# wdt.net
KiCad netlist of a schematic drawn in EAGLE
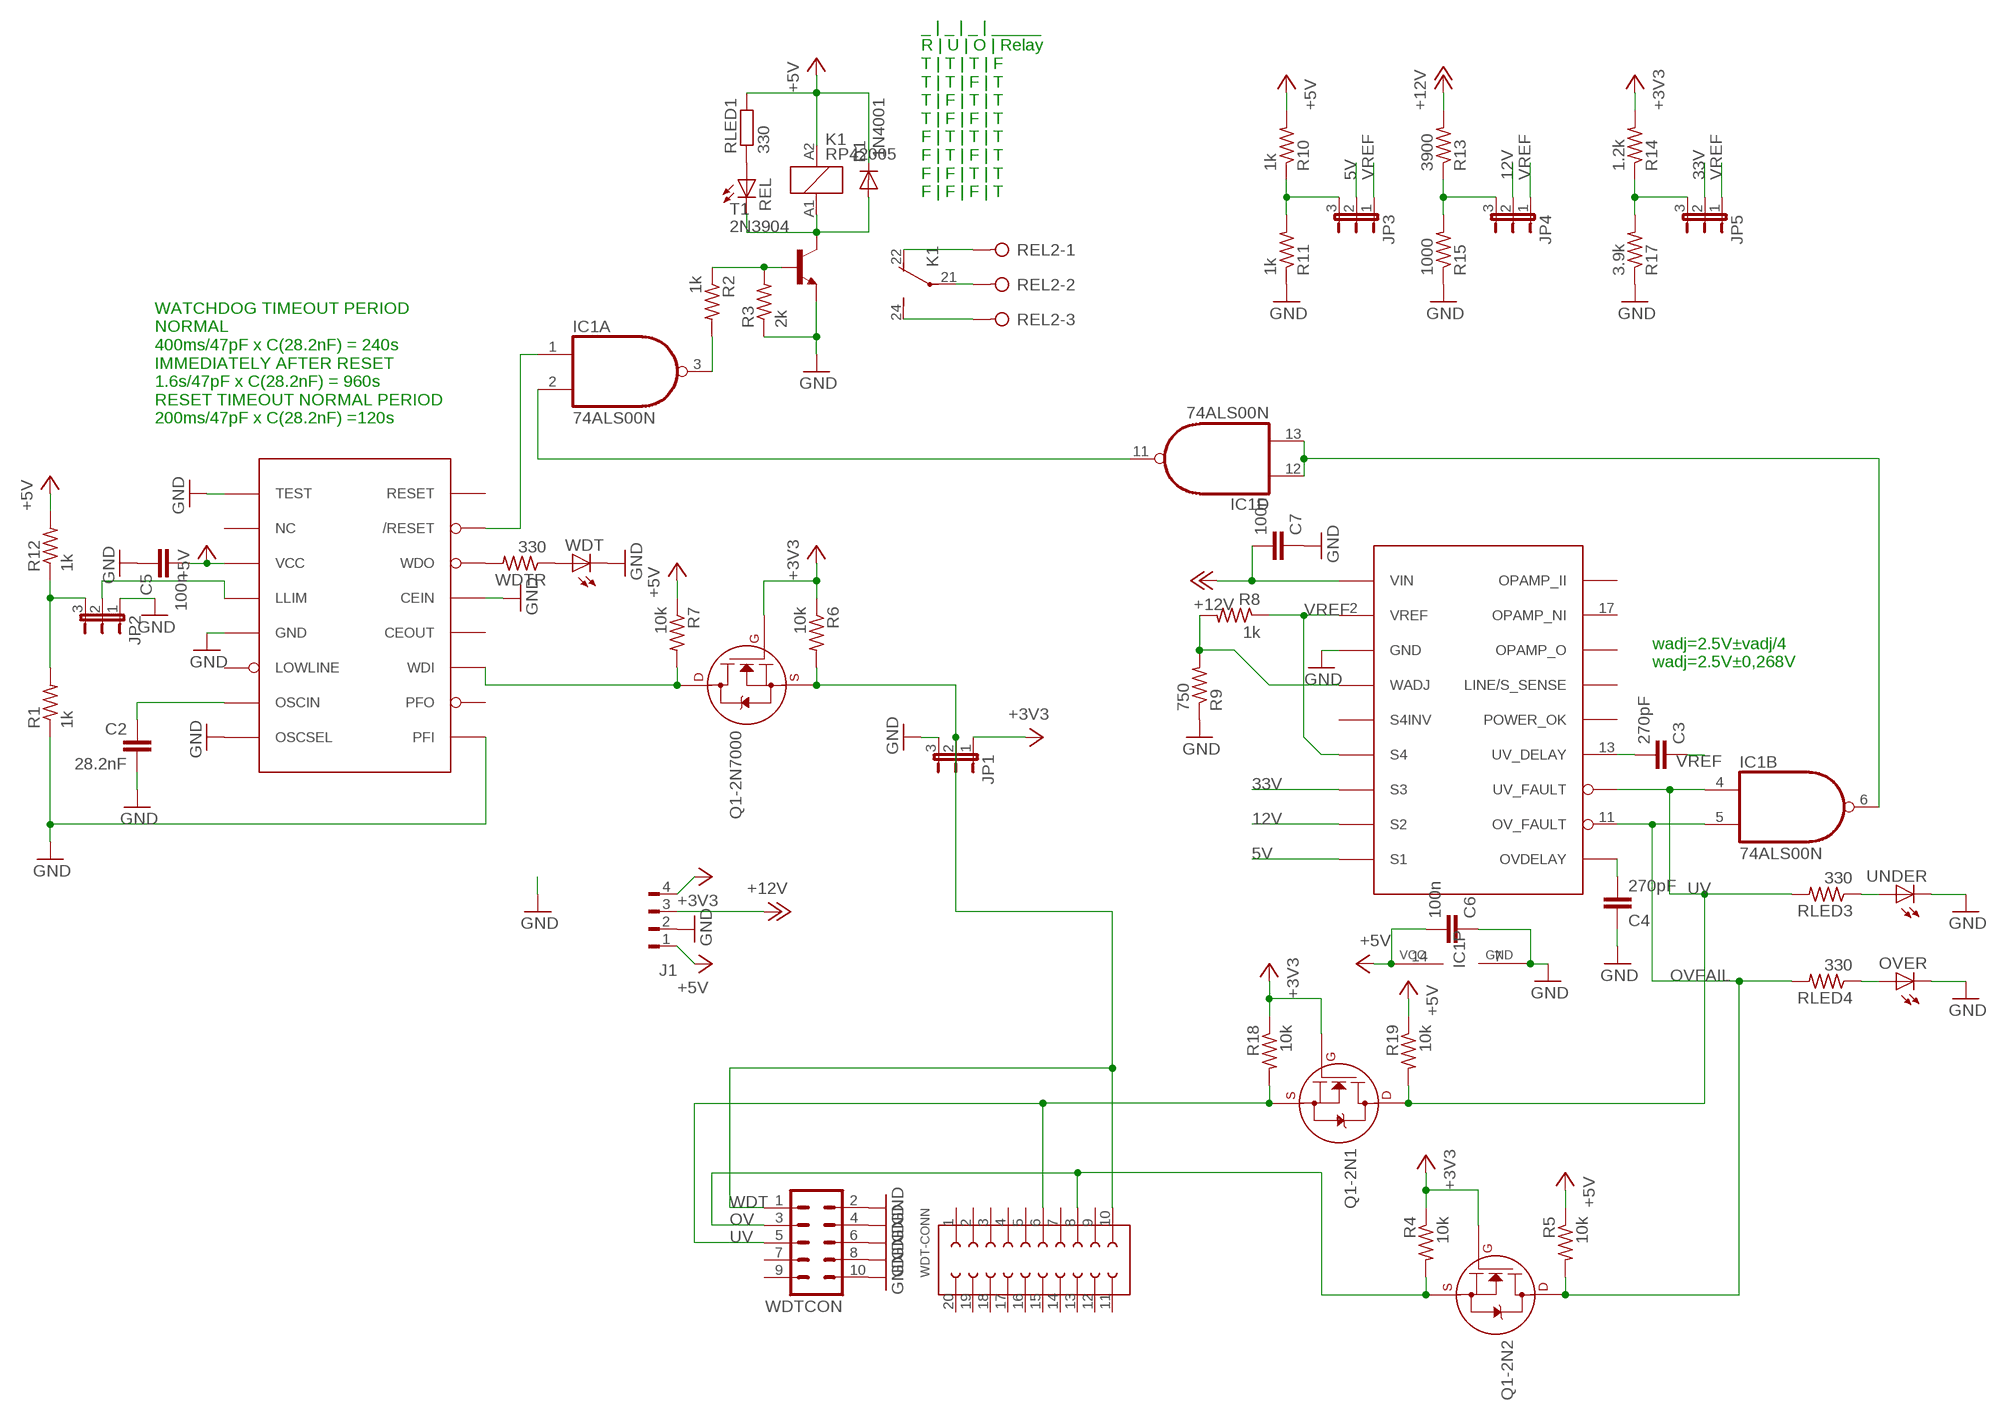
[diagram p0: schematic, sheet 1]

(export (version "E")
  (design (tool "Eeschema 10.0.6"))
  (components
    (comp (ref "C2")
      (value "28.2nF")
      (footprint "eagle-import:C050-025X075")
      (libsource (lib "eagle-import") (part "C-EU050-025X075"))
    )
    (comp (ref "C3")
      (value "270pF")
      (footprint "eagle-import:C050-025X075")
      (libsource (lib "eagle-import") (part "C-EU050-025X075"))
    )
    (comp (ref "C4")
      (value "270pF")
      (footprint "eagle-import:C050-025X075")
      (libsource (lib "eagle-import") (part "C-EU050-025X075"))
    )
    (comp (ref "C5")
      (value "100n")
      (footprint "eagle-import:C050-025X075")
      (libsource (lib "eagle-import") (part "C-EU050-025X075"))
    )
    (comp (ref "C6")
      (value "100n")
      (footprint "eagle-import:C050-025X075")
      (libsource (lib "eagle-import") (part "C-EU050-025X075"))
    )
    (comp (ref "C7")
      (value "100n")
      (footprint "eagle-import:C050-025X075")
      (libsource (lib "eagle-import") (part "C-EU050-025X075"))
    )
    (comp (ref "D1")
      (value "1N4001")
      (footprint "eagle-import:DO41-10")
      (libsource (lib "eagle-import") (part "1N4004"))
    )
    (comp (ref "IC1")
      (value "74ALS00N")
      (footprint "eagle-import:DIL14")
      (libsource (lib "eagle-import") (part "7400NALS"))
    )
    (comp (ref "J1")
      (value "FLOP-4W827001")
      (footprint "eagle-import:827001")
      (libsource (lib "eagle-import") (part "FLOP-4W827001"))
    )
    (comp (ref "JP1")
      (value "JP2E")
      (footprint "eagle-import:JP2")
      (libsource (lib "eagle-import") (part "JP2E"))
    )
    (comp (ref "JP2")
      (value "JP2E")
      (footprint "eagle-import:JP2")
      (libsource (lib "eagle-import") (part "JP2E"))
    )
    (comp (ref "JP3")
      (value "JP2E")
      (footprint "eagle-import:JP2")
      (libsource (lib "eagle-import") (part "JP2E"))
    )
    (comp (ref "JP4")
      (value "JP2E")
      (footprint "eagle-import:JP2")
      (libsource (lib "eagle-import") (part "JP2E"))
    )
    (comp (ref "JP5")
      (value "JP2E")
      (footprint "eagle-import:JP2")
      (libsource (lib "eagle-import") (part "JP2E"))
    )
    (comp (ref "K1")
      (value "RP42005")
      (footprint "eagle-import:RP420")
      (fields (field (name "MF") "TYCO ELECTRONICS") (field (name "MPN") "RP420024"))
      (libsource (lib "eagle-import") (part "RP42?0024"))
    )
    (comp (ref "OVER")
      (value "LED3MM")
      (footprint "eagle-import:LED3MM")
      (libsource (lib "eagle-import") (part "LED3MM"))
    )
    (comp (ref "Q1-2N1")
      (value "2N7000_TO92")
      (footprint "eagle-import:TO-92")
      (libsource (lib "eagle-import") (part "2N700_TO920"))
    )
    (comp (ref "Q1-2N2")
      (value "2N7000_TO92")
      (footprint "eagle-import:TO-92")
      (libsource (lib "eagle-import") (part "2N700_TO920"))
    )
    (comp (ref "Q1-2N7000")
      (value "2N7000_TO92")
      (footprint "eagle-import:TO-92")
      (libsource (lib "eagle-import") (part "2N700_TO920"))
    )
    (comp (ref "R1")
      (value "1k")
      (footprint "eagle-import:0207_10")
      (libsource (lib "eagle-import") (part "R-US_0207/10"))
    )
    (comp (ref "R2")
      (value "1k")
      (footprint "eagle-import:0207_10")
      (libsource (lib "eagle-import") (part "R-US_0207/10"))
    )
    (comp (ref "R3")
      (value "2k")
      (footprint "eagle-import:0207_10")
      (libsource (lib "eagle-import") (part "R-US_0207/10"))
    )
    (comp (ref "R4")
      (value "10k")
      (footprint "eagle-import:0207_10")
      (libsource (lib "eagle-import") (part "R-US_0207/10"))
    )
    (comp (ref "R5")
      (value "10k")
      (footprint "eagle-import:0207_10")
      (libsource (lib "eagle-import") (part "R-US_0207/10"))
    )
    (comp (ref "R6")
      (value "10k")
      (footprint "eagle-import:0207_10")
      (libsource (lib "eagle-import") (part "R-US_0207/10"))
    )
    (comp (ref "R7")
      (value "10k")
      (footprint "eagle-import:0207_10")
      (libsource (lib "eagle-import") (part "R-US_0207/10"))
    )
    (comp (ref "R8")
      (value "1k")
      (footprint "eagle-import:0207_10")
      (libsource (lib "eagle-import") (part "R-US_0207/10"))
    )
    (comp (ref "R9")
      (value "750")
      (footprint "eagle-import:0207_10")
      (libsource (lib "eagle-import") (part "R-US_0207/10"))
    )
    (comp (ref "R10")
      (value "1k")
      (footprint "eagle-import:0207_10")
      (libsource (lib "eagle-import") (part "R-US_0207/10"))
    )
    (comp (ref "R11")
      (value "1k")
      (footprint "eagle-import:0207_10")
      (libsource (lib "eagle-import") (part "R-US_0207/10"))
    )
    (comp (ref "R12")
      (value "1k")
      (footprint "eagle-import:0207_10")
      (libsource (lib "eagle-import") (part "R-US_0207/10"))
    )
    (comp (ref "R13")
      (value "3900")
      (footprint "eagle-import:0207_10")
      (libsource (lib "eagle-import") (part "R-US_0207/10"))
    )
    (comp (ref "R14")
      (value "1.2k")
      (footprint "eagle-import:0207_10")
      (libsource (lib "eagle-import") (part "R-US_0207/10"))
    )
    (comp (ref "R15")
      (value "1000")
      (footprint "eagle-import:0207_10")
      (libsource (lib "eagle-import") (part "R-US_0207/10"))
    )
    (comp (ref "R17")
      (value "3.9k")
      (footprint "eagle-import:0207_10")
      (libsource (lib "eagle-import") (part "R-US_0207/10"))
    )
    (comp (ref "R18")
      (value "10k")
      (footprint "eagle-import:0207_10")
      (libsource (lib "eagle-import") (part "R-US_0207/10"))
    )
    (comp (ref "R19")
      (value "10k")
      (footprint "eagle-import:0207_10")
      (libsource (lib "eagle-import") (part "R-US_0207/10"))
    )
    (comp (ref "REL")
      (value "LED3MM")
      (footprint "eagle-import:LED3MM")
      (libsource (lib "eagle-import") (part "LED3MM"))
    )
    (comp (ref "REL2")
      (value "W237-3E")
      (footprint "eagle-import:W237-3E")
      (fields (field (name "OC_FARNELL") "unknown") (field (name "OC_NEWARK") "unknown"))
      (libsource (lib "eagle-import") (part "W237-3E"))
    )
    (comp (ref "RLED1")
      (value "330")
      (footprint "eagle-import:0207_10")
      (libsource (lib "eagle-import") (part "R-EU_0207/10"))
    )
    (comp (ref "RLED3")
      (value "330")
      (footprint "eagle-import:0207_10")
      (libsource (lib "eagle-import") (part "R-US_0207/10"))
    )
    (comp (ref "RLED4")
      (value "330")
      (footprint "eagle-import:0207_10")
      (libsource (lib "eagle-import") (part "R-US_0207/10"))
    )
    (comp (ref "T1")
      (value "2N3904")
      (footprint "eagle-import:TO92")
      (libsource (lib "eagle-import") (part "2N3904"))
    )
    (comp (ref "U$1")
      (value "UC3903")
      (footprint "eagle-import:DIL18")
      (libsource (lib "eagle-import") (part "UC3903"))
    )
    (comp (ref "U$2")
      (value "MAX697")
      (footprint "eagle-import:DIL16")
      (libsource (lib "eagle-import") (part "MAX697"))
    )
    (comp (ref "UNDER")
      (value "LED3MM")
      (footprint "eagle-import:LED3MM")
      (libsource (lib "eagle-import") (part "LED3MM"))
    )
    (comp (ref "WDT")
      (value "LED3MM")
      (footprint "eagle-import:LED3MM")
      (libsource (lib "eagle-import") (part "LED3MM"))
    )
    (comp (ref "WDT-CONN")
      (value "623X2021021")
      (footprint "eagle-import:623X2021021")
      (libsource (lib "eagle-import") (part "623X2021021"))
    )
    (comp (ref "WDTCON")
      (value "ML10")
      (footprint "eagle-import:ML10")
      (libsource (lib "eagle-import") (part "ML10"))
    )
    (comp (ref "WDTR")
      (value "330")
      (footprint "eagle-import:0207_10")
      (libsource (lib "eagle-import") (part "R-US_0207/10"))
    )
  )
  (nets
    (net (code "1") (name "+3V3") (class "Default")
      (node (ref "J1") (pin "4") (pinfunction "4_4") (pintype "passive"))
      (node (ref "JP1") (pin "1") (pinfunction "1_1") (pintype "passive"))
      (node (ref "Q1-2N1") (pin "2") (pinfunction "G_2") (pintype "tri_state"))
      (node (ref "Q1-2N2") (pin "2") (pinfunction "G_2") (pintype "tri_state"))
      (node (ref "Q1-2N7000") (pin "2") (pinfunction "G_2") (pintype "tri_state"))
      (node (ref "R14") (pin "2") (pinfunction "2_2") (pintype "passive"))
      (node (ref "R18") (pin "1") (pinfunction "1_1") (pintype "passive"))
      (node (ref "R4") (pin "1") (pinfunction "1_1") (pintype "passive"))
      (node (ref "R6") (pin "1") (pinfunction "1_1") (pintype "passive"))
    )
    (net (code "2") (name "+5V") (class "Default")
      (node (ref "C5") (pin "2") (pinfunction "2_2") (pintype "passive"))
      (node (ref "C6") (pin "2") (pinfunction "2_2") (pintype "passive"))
      (node (ref "D1") (pin "C") (pinfunction "C_C") (pintype "passive"))
      (node (ref "IC1") (pin "14") (pinfunction "VCC_14") (pintype "power_in"))
      (node (ref "J1") (pin "1") (pinfunction "1_1") (pintype "passive"))
      (node (ref "K1") (pin "A2") (pinfunction "1_A2") (pintype "passive"))
      (node (ref "R10") (pin "2") (pinfunction "2_2") (pintype "passive"))
      (node (ref "R12") (pin "2") (pinfunction "2_2") (pintype "passive"))
      (node (ref "R19") (pin "1") (pinfunction "1_1") (pintype "passive"))
      (node (ref "R5") (pin "1") (pinfunction "1_1") (pintype "passive"))
      (node (ref "R7") (pin "1") (pinfunction "1_1") (pintype "passive"))
      (node (ref "RLED1") (pin "2") (pinfunction "2_2") (pintype "passive"))
      (node (ref "U$2") (pin "3") (pinfunction "VCC_3") (pintype "bidirectional"))
    )
    (net (code "3") (name "+12V") (class "Default")
      (node (ref "C7") (pin "2") (pinfunction "2_2") (pintype "passive"))
      (node (ref "J1") (pin "3") (pinfunction "3_3") (pintype "passive"))
      (node (ref "R13") (pin "2") (pinfunction "2_2") (pintype "passive"))
      (node (ref "U$1") (pin "1") (pinfunction "VIN_1") (pintype "bidirectional"))
    )
    (net (code "4") (name "/5V") (class "Default")
      (node (ref "JP3") (pin "2") (pinfunction "2_2") (pintype "passive"))
      (node (ref "U$1") (pin "9") (pinfunction "S1_9") (pintype "bidirectional"))
    )
    (net (code "5") (name "/12V") (class "Default")
      (node (ref "JP4") (pin "2") (pinfunction "2_2") (pintype "passive"))
      (node (ref "U$1") (pin "8") (pinfunction "S2_8") (pintype "bidirectional"))
    )
    (net (code "6") (name "/33V") (class "Default")
      (node (ref "JP5") (pin "2") (pinfunction "2_2") (pintype "passive"))
      (node (ref "U$1") (pin "7") (pinfunction "S3_7") (pintype "bidirectional"))
    )
    (net (code "7") (name "/OV") (class "Default")
      (node (ref "Q1-2N2") (pin "1") (pinfunction "S_1") (pintype "bidirectional"))
      (node (ref "R4") (pin "2") (pinfunction "2_2") (pintype "passive"))
      (node (ref "WDT-CONN") (pin "8") (pinfunction "8_8") (pintype "passive"))
      (node (ref "WDTCON") (pin "3") (pinfunction "3_3") (pintype "passive"))
    )
    (net (code "8") (name "/OVFAIL") (class "Default")
      (node (ref "IC1") (pin "5") (pinfunction "I1_5") (pintype "input"))
      (node (ref "Q1-2N2") (pin "3") (pinfunction "D_3") (pintype "bidirectional"))
      (node (ref "R5") (pin "2") (pinfunction "2_2") (pintype "passive"))
      (node (ref "RLED4") (pin "2") (pinfunction "2_2") (pintype "passive"))
      (node (ref "U$1") (pin "11") (pinfunction "OV_FAULT_11") (pintype "bidirectional"))
    )
    (net (code "9") (name "/UV") (class "Default")
      (node (ref "IC1") (pin "4") (pinfunction "I0_4") (pintype "input"))
      (node (ref "Q1-2N1") (pin "1") (pinfunction "S_1") (pintype "bidirectional"))
      (node (ref "Q1-2N1") (pin "3") (pinfunction "D_3") (pintype "bidirectional"))
      (node (ref "R18") (pin "2") (pinfunction "2_2") (pintype "passive"))
      (node (ref "R19") (pin "2") (pinfunction "2_2") (pintype "passive"))
      (node (ref "RLED3") (pin "2") (pinfunction "2_2") (pintype "passive"))
      (node (ref "U$1") (pin "12") (pinfunction "UV_FAULT_12") (pintype "bidirectional"))
      (node (ref "WDT-CONN") (pin "6") (pinfunction "6_6") (pintype "passive"))
      (node (ref "WDTCON") (pin "5") (pinfunction "5_5") (pintype "passive"))
    )
    (net (code "10") (name "/VREF") (class "Default")
      (node (ref "C3") (pin "1") (pinfunction "1_1") (pintype "passive"))
      (node (ref "JP3") (pin "1") (pinfunction "1_1") (pintype "passive"))
      (node (ref "JP4") (pin "1") (pinfunction "1_1") (pintype "passive"))
      (node (ref "JP5") (pin "1") (pinfunction "1_1") (pintype "passive"))
      (node (ref "R8") (pin "1") (pinfunction "1_1") (pintype "passive"))
      (node (ref "U$1") (pin "2") (pinfunction "VREF_2") (pintype "bidirectional"))
      (node (ref "U$1") (pin "6") (pinfunction "S4_6") (pintype "bidirectional"))
    )
    (net (code "11") (name "/WDT") (class "Default")
      (node (ref "JP1") (pin "2") (pinfunction "2_2") (pintype "passive"))
      (node (ref "Q1-2N7000") (pin "1") (pinfunction "S_1") (pintype "bidirectional"))
      (node (ref "R6") (pin "2") (pinfunction "2_2") (pintype "passive"))
      (node (ref "WDT-CONN") (pin "10") (pinfunction "10_10") (pintype "passive"))
      (node (ref "WDTCON") (pin "1") (pinfunction "1_1") (pintype "passive"))
    )
    (net (code "12") (name "GND") (class "Default")
      (node (ref "C2") (pin "2") (pinfunction "2_2") (pintype "passive"))
      (node (ref "C4") (pin "1") (pinfunction "1_1") (pintype "passive"))
      (node (ref "C5") (pin "1") (pinfunction "1_1") (pintype "passive"))
      (node (ref "C6") (pin "1") (pinfunction "1_1") (pintype "passive"))
      (node (ref "C7") (pin "1") (pinfunction "1_1") (pintype "passive"))
      (node (ref "IC1") (pin "7") (pinfunction "GND_7") (pintype "power_in"))
      (node (ref "J1") (pin "2") (pinfunction "2_2") (pintype "passive"))
      (node (ref "JP1") (pin "3") (pinfunction "3_3") (pintype "passive"))
      (node (ref "JP2") (pin "1") (pinfunction "1_1") (pintype "passive"))
      (node (ref "OVER") (pin "K") (pinfunction "C_K") (pintype "passive"))
      (node (ref "R1") (pin "1") (pinfunction "1_1") (pintype "passive"))
      (node (ref "R11") (pin "1") (pinfunction "1_1") (pintype "passive"))
      (node (ref "R15") (pin "1") (pinfunction "1_1") (pintype "passive"))
      (node (ref "R17") (pin "1") (pinfunction "1_1") (pintype "passive"))
      (node (ref "R3") (pin "1") (pinfunction "1_1") (pintype "passive"))
      (node (ref "R9") (pin "1") (pinfunction "1_1") (pintype "passive"))
      (node (ref "T1") (pin "3") (pinfunction "E_3") (pintype "passive"))
      (node (ref "U$1") (pin "3") (pinfunction "GND_3") (pintype "bidirectional"))
      (node (ref "U$2") (pin "1") (pinfunction "TEST_1") (pintype "bidirectional"))
      (node (ref "U$2") (pin "13") (pinfunction "CEIN_13") (pintype "bidirectional"))
      (node (ref "U$2") (pin "5") (pinfunction "GND_5") (pintype "bidirectional"))
      (node (ref "U$2") (pin "8") (pinfunction "OSCSEL_8") (pintype "bidirectional"))
      (node (ref "U$2") (pin "9") (pinfunction "PFI_9") (pintype "bidirectional"))
      (node (ref "UNDER") (pin "K") (pinfunction "C_K") (pintype "passive"))
      (node (ref "WDT") (pin "K") (pinfunction "C_K") (pintype "passive"))
      (node (ref "WDTCON") (pin "10") (pinfunction "10_10") (pintype "passive"))
      (node (ref "WDTCON") (pin "2") (pinfunction "2_2") (pintype "passive"))
      (node (ref "WDTCON") (pin "4") (pinfunction "4_4") (pintype "passive"))
      (node (ref "WDTCON") (pin "6") (pinfunction "6_6") (pintype "passive"))
      (node (ref "WDTCON") (pin "8") (pinfunction "8_8") (pintype "passive"))
    )
    (net (code "13") (name "Net-(IC1A-I0)") (class "Default")
      (node (ref "IC1") (pin "1") (pinfunction "I0_1") (pintype "input"))
      (node (ref "U$2") (pin "15") (pinfunction "/RESET_15") (pintype "bidirectional"))
    )
    (net (code "14") (name "Net-(IC1A-I1)") (class "Default")
      (node (ref "IC1") (pin "11") (pinfunction "O_11") (pintype "output"))
      (node (ref "IC1") (pin "2") (pinfunction "I1_2") (pintype "input"))
    )
    (net (code "15") (name "Net-(IC1A-O)") (class "Default")
      (node (ref "IC1") (pin "3") (pinfunction "O_3") (pintype "output"))
      (node (ref "R2") (pin "2") (pinfunction "2_2") (pintype "passive"))
    )
    (net (code "16") (name "Net-(IC1B-O)") (class "Default")
      (node (ref "IC1") (pin "12") (pinfunction "I0_12") (pintype "input"))
      (node (ref "IC1") (pin "13") (pinfunction "I1_13") (pintype "input"))
      (node (ref "IC1") (pin "6") (pinfunction "O_6") (pintype "output"))
    )
    (net (code "17") (name "Net-(JP2-Pad3)") (class "Default")
      (node (ref "JP2") (pin "3") (pinfunction "3_3") (pintype "passive"))
      (node (ref "R1") (pin "2") (pinfunction "2_2") (pintype "passive"))
      (node (ref "R12") (pin "1") (pinfunction "1_1") (pintype "passive"))
    )
    (net (code "18") (name "Net-(JP3-Pad3)") (class "Default")
      (node (ref "JP3") (pin "3") (pinfunction "3_3") (pintype "passive"))
      (node (ref "R10") (pin "1") (pinfunction "1_1") (pintype "passive"))
      (node (ref "R11") (pin "2") (pinfunction "2_2") (pintype "passive"))
    )
    (net (code "19") (name "Net-(JP4-Pad3)") (class "Default")
      (node (ref "JP4") (pin "3") (pinfunction "3_3") (pintype "passive"))
      (node (ref "R13") (pin "1") (pinfunction "1_1") (pintype "passive"))
      (node (ref "R15") (pin "2") (pinfunction "2_2") (pintype "passive"))
    )
    (net (code "20") (name "Net-(JP5-Pad3)") (class "Default")
      (node (ref "JP5") (pin "3") (pinfunction "3_3") (pintype "passive"))
      (node (ref "R14") (pin "1") (pinfunction "1_1") (pintype "passive"))
      (node (ref "R17") (pin "2") (pinfunction "2_2") (pintype "passive"))
    )
    (net (code "21") (name "Net-(K1A-2)") (class "Default")
      (node (ref "D1") (pin "A") (pinfunction "A_A") (pintype "passive"))
      (node (ref "K1") (pin "A1") (pinfunction "2_A1") (pintype "passive"))
      (node (ref "REL") (pin "K") (pinfunction "C_K") (pintype "passive"))
      (node (ref "T1") (pin "1") (pinfunction "C_1") (pintype "passive"))
    )
    (net (code "22") (name "Net-(K1C-O)") (class "Default")
      (node (ref "K1") (pin "22") (pinfunction "O_22") (pintype "passive"))
      (node (ref "REL2") (pin "1") (pinfunction "KL_1") (pintype "passive"))
    )
    (net (code "23") (name "Net-(K1C-P)") (class "Default")
      (node (ref "K1") (pin "21") (pinfunction "P_21") (pintype "passive"))
      (node (ref "REL2") (pin "2") (pinfunction "KL_2") (pintype "passive"))
    )
    (net (code "24") (name "Net-(K1C-S)") (class "Default")
      (node (ref "K1") (pin "24") (pinfunction "S_24") (pintype "passive"))
      (node (ref "REL2") (pin "3") (pinfunction "KL_3") (pintype "passive"))
    )
    (net (code "25") (name "Net-(OVER-PadA)") (class "Default")
      (node (ref "OVER") (pin "A") (pinfunction "A_A") (pintype "passive"))
      (node (ref "RLED4") (pin "1") (pinfunction "1_1") (pintype "passive"))
    )
    (net (code "26") (name "Net-(Q1-2N7000-D)") (class "Default")
      (node (ref "Q1-2N7000") (pin "3") (pinfunction "D_3") (pintype "bidirectional"))
      (node (ref "R7") (pin "2") (pinfunction "2_2") (pintype "passive"))
      (node (ref "U$2") (pin "11") (pinfunction "WDI_11") (pintype "bidirectional"))
    )
    (net (code "27") (name "Net-(REL-PadA)") (class "Default")
      (node (ref "REL") (pin "A") (pinfunction "A_A") (pintype "passive"))
      (node (ref "RLED1") (pin "1") (pinfunction "1_1") (pintype "passive"))
    )
    (net (code "28") (name "Net-(RLED3-Pad1)") (class "Default")
      (node (ref "RLED3") (pin "1") (pinfunction "1_1") (pintype "passive"))
      (node (ref "UNDER") (pin "A") (pinfunction "A_A") (pintype "passive"))
    )
    (net (code "29") (name "Net-(T1-B)") (class "Default")
      (node (ref "R2") (pin "1") (pinfunction "1_1") (pintype "passive"))
      (node (ref "R3") (pin "2") (pinfunction "2_2") (pintype "passive"))
      (node (ref "T1") (pin "2") (pinfunction "B_2") (pintype "passive"))
    )
    (net (code "30") (name "Net-(U$1-OVDELAY)") (class "Default")
      (node (ref "C4") (pin "2") (pinfunction "2_2") (pintype "passive"))
      (node (ref "U$1") (pin "10") (pinfunction "OVDELAY_10") (pintype "bidirectional"))
    )
    (net (code "31") (name "Net-(U$1-UV_DELAY)") (class "Default")
      (node (ref "C3") (pin "2") (pinfunction "2_2") (pintype "passive"))
      (node (ref "U$1") (pin "13") (pinfunction "UV_DELAY_13") (pintype "bidirectional"))
    )
    (net (code "32") (name "Net-(U$1-WADJ)") (class "Default")
      (node (ref "R8") (pin "2") (pinfunction "2_2") (pintype "passive"))
      (node (ref "R9") (pin "2") (pinfunction "2_2") (pintype "passive"))
      (node (ref "U$1") (pin "4") (pinfunction "WADJ_4") (pintype "bidirectional"))
    )
    (net (code "33") (name "Net-(U$2-LLIM)") (class "Default")
      (node (ref "JP2") (pin "2") (pinfunction "2_2") (pintype "passive"))
      (node (ref "U$2") (pin "4") (pinfunction "LLIM_4") (pintype "bidirectional"))
    )
    (net (code "34") (name "Net-(U$2-OSCIN)") (class "Default")
      (node (ref "C2") (pin "1") (pinfunction "1_1") (pintype "passive"))
      (node (ref "U$2") (pin "7") (pinfunction "OSCIN_7") (pintype "bidirectional"))
    )
    (net (code "35") (name "Net-(U$2-WDO)") (class "Default")
      (node (ref "U$2") (pin "14") (pinfunction "WDO_14") (pintype "bidirectional"))
      (node (ref "WDTR") (pin "2") (pinfunction "2_2") (pintype "passive"))
    )
    (net (code "36") (name "Net-(WDT-PadA)") (class "Default")
      (node (ref "WDT") (pin "A") (pinfunction "A_A") (pintype "passive"))
      (node (ref "WDTR") (pin "1") (pinfunction "1_1") (pintype "passive"))
    )
    (net (code "37") (name "unconnected-(U$1-LINE{slash}S_SENSE-Pad15)") (class "Default")
      (node (ref "U$1") (pin "15") (pinfunction "LINE/S_SENSE_15") (pintype "bidirectional"))
    )
    (net (code "38") (name "unconnected-(U$1-OPAMP_II-Pad18)") (class "Default")
      (node (ref "U$1") (pin "18") (pinfunction "OPAMP_II_18") (pintype "bidirectional"))
    )
    (net (code "39") (name "unconnected-(U$1-OPAMP_NI-Pad17)") (class "Default")
      (node (ref "U$1") (pin "17") (pinfunction "OPAMP_NI_17") (pintype "bidirectional"))
    )
    (net (code "40") (name "unconnected-(U$1-OPAMP_O-Pad16)") (class "Default")
      (node (ref "U$1") (pin "16") (pinfunction "OPAMP_O_16") (pintype "bidirectional"))
    )
    (net (code "41") (name "unconnected-(U$1-POWER_OK-Pad14)") (class "Default")
      (node (ref "U$1") (pin "14") (pinfunction "POWER_OK_14") (pintype "bidirectional"))
    )
    (net (code "42") (name "unconnected-(U$1-S4INV-Pad5)") (class "Default")
      (node (ref "U$1") (pin "5") (pinfunction "S4INV_5") (pintype "bidirectional"))
    )
    (net (code "43") (name "unconnected-(U$2-CEOUT-Pad12)") (class "Default")
      (node (ref "U$2") (pin "12") (pinfunction "CEOUT_12") (pintype "bidirectional"))
    )
    (net (code "44") (name "unconnected-(U$2-LOWLINE-Pad6)") (class "Default")
      (node (ref "U$2") (pin "6") (pinfunction "LOWLINE_6") (pintype "bidirectional"))
    )
    (net (code "45") (name "unconnected-(U$2-NC-Pad2)") (class "Default")
      (node (ref "U$2") (pin "2") (pinfunction "NC_2") (pintype "bidirectional"))
    )
    (net (code "46") (name "unconnected-(U$2-PFO-Pad10)") (class "Default")
      (node (ref "U$2") (pin "10") (pinfunction "PFO_10") (pintype "bidirectional"))
    )
    (net (code "47") (name "unconnected-(U$2-RESET-Pad16)") (class "Default")
      (node (ref "U$2") (pin "16") (pinfunction "RESET_16") (pintype "bidirectional"))
    )
    (net (code "48") (name "unconnected-(WDT-CONN-Pad1)") (class "Default")
      (node (ref "WDT-CONN") (pin "1") (pinfunction "1_1") (pintype "passive"))
    )
    (net (code "49") (name "unconnected-(WDT-CONN-Pad2)") (class "Default")
      (node (ref "WDT-CONN") (pin "2") (pinfunction "2_2") (pintype "passive"))
    )
    (net (code "50") (name "unconnected-(WDT-CONN-Pad3)") (class "Default")
      (node (ref "WDT-CONN") (pin "3") (pinfunction "3_3") (pintype "passive"))
    )
    (net (code "51") (name "unconnected-(WDT-CONN-Pad4)") (class "Default")
      (node (ref "WDT-CONN") (pin "4") (pinfunction "4_4") (pintype "passive"))
    )
    (net (code "52") (name "unconnected-(WDT-CONN-Pad5)") (class "Default")
      (node (ref "WDT-CONN") (pin "5") (pinfunction "5_5") (pintype "passive"))
    )
    (net (code "53") (name "unconnected-(WDT-CONN-Pad7)") (class "Default")
      (node (ref "WDT-CONN") (pin "7") (pinfunction "7_7") (pintype "passive"))
    )
    (net (code "54") (name "unconnected-(WDT-CONN-Pad9)") (class "Default")
      (node (ref "WDT-CONN") (pin "9") (pinfunction "9_9") (pintype "passive"))
    )
    (net (code "55") (name "unconnected-(WDT-CONN-Pad11)") (class "Default")
      (node (ref "WDT-CONN") (pin "11") (pinfunction "11_11") (pintype "passive"))
    )
    (net (code "56") (name "unconnected-(WDT-CONN-Pad12)") (class "Default")
      (node (ref "WDT-CONN") (pin "12") (pinfunction "12_12") (pintype "passive"))
    )
    (net (code "57") (name "unconnected-(WDT-CONN-Pad13)") (class "Default")
      (node (ref "WDT-CONN") (pin "13") (pinfunction "13_13") (pintype "passive"))
    )
    (net (code "58") (name "unconnected-(WDT-CONN-Pad14)") (class "Default")
      (node (ref "WDT-CONN") (pin "14") (pinfunction "14_14") (pintype "passive"))
    )
    (net (code "59") (name "unconnected-(WDT-CONN-Pad15)") (class "Default")
      (node (ref "WDT-CONN") (pin "15") (pinfunction "15_15") (pintype "passive"))
    )
    (net (code "60") (name "unconnected-(WDT-CONN-Pad16)") (class "Default")
      (node (ref "WDT-CONN") (pin "16") (pinfunction "16_16") (pintype "passive"))
    )
    (net (code "61") (name "unconnected-(WDT-CONN-Pad17)") (class "Default")
      (node (ref "WDT-CONN") (pin "17") (pinfunction "17_17") (pintype "passive"))
    )
    (net (code "62") (name "unconnected-(WDT-CONN-Pad18)") (class "Default")
      (node (ref "WDT-CONN") (pin "18") (pinfunction "18_18") (pintype "passive"))
    )
    (net (code "63") (name "unconnected-(WDT-CONN-Pad19)") (class "Default")
      (node (ref "WDT-CONN") (pin "19") (pinfunction "19_19") (pintype "passive"))
    )
    (net (code "64") (name "unconnected-(WDT-CONN-Pad20)") (class "Default")
      (node (ref "WDT-CONN") (pin "20") (pinfunction "20_20") (pintype "passive"))
    )
    (net (code "65") (name "unconnected-(WDTCON-Pad7)") (class "Default")
      (node (ref "WDTCON") (pin "7") (pinfunction "7_7") (pintype "passive"))
    )
    (net (code "66") (name "unconnected-(WDTCON-Pad9)") (class "Default")
      (node (ref "WDTCON") (pin "9") (pinfunction "9_9") (pintype "passive"))
    )
  )
)
